# Sheet1.net
KiCad netlist of a schematic drawn in Altium Designer
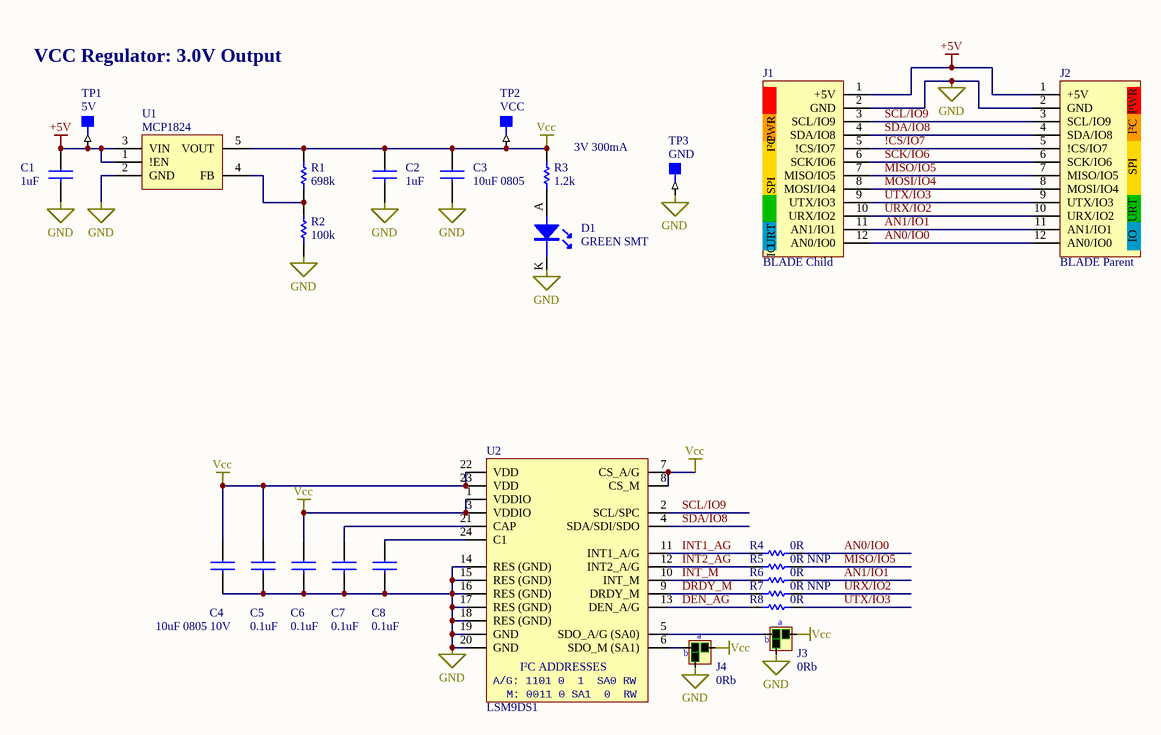
[diagram p0: Sheet1.SchDoc]

(export (version "E")
  (design (tool "Eeschema 10.0.6"))
  (components
    (comp (ref "C1")
      (value "1uF")
      (footprint "0603")
      (fields
        (field (name "4. DIGI-KEY PART NUMBER") "587-1251-2-ND")
        (field (name "3. MANUFACTURER PART NUMBER") "EMK107BJ105KA-T")
        (field (name "5. INTERNAL PART NUMBER") "100009")
        (field (name "7. MODIFIED BY") "JRL")
      )
      (libsource (lib "Blackline Master Schematic Library") (part "CAPACITOR NON-POLARIZED"))
    )
    (comp (ref "C2")
      (value "1uF")
      (footprint "0603")
      (fields
        (field (name "4. DIGI-KEY PART NUMBER") "587-1251-2-ND")
        (field (name "3. MANUFACTURER PART NUMBER") "EMK107BJ105KA-T")
        (field (name "5. INTERNAL PART NUMBER") "100009")
        (field (name "7. MODIFIED BY") "JRL")
      )
      (libsource (lib "Blackline Master Schematic Library") (part "CAPACITOR NON-POLARIZED"))
    )
    (comp (ref "C3")
      (value "10uF 0805")
      (footprint "0805")
      (fields
        (field (name "4. DIGI-KEY PART NUMBER") "587-1300-1-ND")
        (field (name "3. MANUFACTURER PART NUMBER") "LMK212BJ106KG-T")
        (field (name "5. INTERNAL PART NUMBER") "100006")
        (field (name "7. MODIFIED BY") "JRL")
      )
      (libsource (lib "Blackline Master Schematic Library") (part "CAPACITOR NON-POLARIZED"))
    )
    (comp (ref "C4")
      (value "10uF 0805 10V")
      (footprint "0805")
      (fields
        (field (name "4. DIGI-KEY PART NUMBER") "587-1300-1-ND")
        (field (name "3. MANUFACTURER PART NUMBER") "LMK212BJ106KG-T")
        (field (name "5. INTERNAL PART NUMBER") "100006")
        (field (name "7. MODIFIED BY") "JRL")
      )
      (libsource (lib "Blackline Master Schematic Library") (part "CAPACITOR NON-POLARIZED"))
    )
    (comp (ref "C5")
      (value "0.1uF")
      (footprint "0603")
      (fields
        (field (name "4. DIGI-KEY PART NUMBER") "445-1316-2-ND")
        (field (name "3. MANUFACTURER PART NUMBER") "C1608X7R1E104K")
        (field (name "5. INTERNAL PART NUMBER") "100130")
        (field (name "7. MODIFIED BY") "JRL")
      )
      (libsource (lib "Blackline Master Schematic Library") (part "CAPACITOR NON-POLARIZED"))
    )
    (comp (ref "C6")
      (value "0.1uF")
      (footprint "0603")
      (fields
        (field (name "4. DIGI-KEY PART NUMBER") "445-1316-2-ND")
        (field (name "3. MANUFACTURER PART NUMBER") "C1608X7R1E104K")
        (field (name "5. INTERNAL PART NUMBER") "100130")
        (field (name "7. MODIFIED BY") "JRL")
      )
      (libsource (lib "Blackline Master Schematic Library") (part "CAPACITOR NON-POLARIZED"))
    )
    (comp (ref "C7")
      (value "0.1uF")
      (footprint "0603")
      (fields
        (field (name "4. DIGI-KEY PART NUMBER") "445-1316-2-ND")
        (field (name "3. MANUFACTURER PART NUMBER") "C1608X7R1E104K")
        (field (name "5. INTERNAL PART NUMBER") "100130")
        (field (name "7. MODIFIED BY") "JRL")
      )
      (libsource (lib "Blackline Master Schematic Library") (part "CAPACITOR NON-POLARIZED"))
    )
    (comp (ref "C8")
      (value "0.1uF")
      (footprint "0603")
      (fields
        (field (name "4. DIGI-KEY PART NUMBER") "445-1316-2-ND")
        (field (name "3. MANUFACTURER PART NUMBER") "C1608X7R1E104K")
        (field (name "5. INTERNAL PART NUMBER") "100130")
        (field (name "7. MODIFIED BY") "JRL")
      )
      (libsource (lib "Blackline Master Schematic Library") (part "CAPACITOR NON-POLARIZED"))
    )
    (comp (ref "D1")
      (value "GREEN SMT")
      (footprint "0603 AK")
      (description "LED")
      (fields
        (field (name "3. MANUFACTURER PART NUMBER") "LTST-C190GKT")
        (field (name "4. DIGI-KEY PART NUMBER") "160-1183-1-ND")
        (field (name "7. MODIFIED BY") "JRL")
      )
      (libsource (lib "*") (part "LED T1-3/4"))
    )
    (comp (ref "J1")
      (value "BLADE Child")
      (footprint "HDR1X12 ENGENUICS CHILD")
      (fields
        (field (name "3. MANUFACTURER PART NUMBER") "68016-412HLF")
        (field (name "4. DIGI-KEY PART NUMBER") "609-3330-ND")
        (field (name "5. INTERNAL PART NUMBER") "100021")
        (field (name "7. MODIFIED BY") "JRL")
      )
      (libsource (lib "Engenuics Master Schematic Library") (part "CONN ENGENUICS BLADE CHILD"))
    )
    (comp (ref "J2")
      (value "BLADE Parent")
      (footprint "HDR1X12 ENGENUICS PARENT")
      (fields
        (field (name "3. MANUFACTURER PART NUMBER") "PPTC121LGBN-RC")
        (field (name "4. DIGI-KEY PART NUMBER") "S5448-ND")
        (field (name "5. INTERNAL PART NUMBER") "100031")
        (field (name "7. MODIFIED BY") "JRL")
      )
      (libsource (lib "Engenuics Master Schematic Library") (part "CONN ENGENUICS BLADE PARENT"))
    )
    (comp (ref "J3")
      (value "0Rb")
      (footprint "0603 SELECTOR")
      (fields
        (field (name "3. MANUFACTURER PART NUMBER") "CRCW06030000Z0EA")
        (field (name "4. DIGI-KEY PART NUMBER") "541-0.0GTR-ND")
        (field (name "5. INTERNAL PART NUMBER") "100075")
        (field (name "7. MODIFIED BY") "JRL")
      )
      (libsource (lib "Engenuics Master Schematic Library") (part "SWITCH RESISTOR SELECTOR"))
    )
    (comp (ref "J4")
      (value "0Rb")
      (footprint "0603 SELECTOR")
      (fields
        (field (name "3. MANUFACTURER PART NUMBER") "CRCW06030000Z0EA")
        (field (name "4. DIGI-KEY PART NUMBER") "541-0.0GTR-ND")
        (field (name "5. INTERNAL PART NUMBER") "100075")
        (field (name "7. MODIFIED BY") "JRL")
      )
      (libsource (lib "Engenuics Master Schematic Library") (part "SWITCH RESISTOR SELECTOR"))
    )
    (comp (ref "R1")
      (value "698k")
      (footprint "0603")
      (fields
        (field (name "4. DIGI-KEY PART NUMBER") "311-698KHRCT-ND")
        (field (name "3. MANUFACTURER PART NUMBER") "RC0603FR-07698KL")
        (field (name "5. INTERNAL PART NUMBER") "100087")
        (field (name "7. MODIFIED BY") "JRL")
      )
      (libsource (lib "Blackline Master Schematic Library") (part "RESISTOR"))
    )
    (comp (ref "R2")
      (value "100k")
      (footprint "0603")
      (fields
        (field (name "4. DIGI-KEY PART NUMBER") "RHM100KGCT-ND")
        (field (name "3. MANUFACTURER PART NUMBER") "MCR03EZPJ104")
        (field (name "5. INTERNAL PART NUMBER") "100078")
        (field (name "7. MODIFIED BY") "JRL")
      )
      (libsource (lib "Blackline Master Schematic Library") (part "RESISTOR"))
    )
    (comp (ref "R3")
      (value "1.2k")
      (footprint "0603")
      (fields
        (field (name "4. DIGI-KEY PART NUMBER") "RHM1.2KGCT-ND")
        (field (name "3. MANUFACTURER PART NUMBER") "MCR03EZPJ122")
        (field (name "5. INTERNAL PART NUMBER") "100076")
        (field (name "7. MODIFIED BY") "JRL")
      )
      (libsource (lib "Blackline Master Schematic Library") (part "RESISTOR"))
    )
    (comp (ref "R4")
      (value "0R")
      (footprint "0603")
      (fields
        (field (name "4. DIGI-KEY PART NUMBER") "541-0.0GTR-ND")
        (field (name "3. MANUFACTURER PART NUMBER") "CRCW06030000Z0EA")
        (field (name "5. INTERNAL PART NUMBER") "100075")
        (field (name "7. MODIFIED BY") "JRL")
      )
      (libsource (lib "Blackline Master Schematic Library") (part "RESISTOR"))
    )
    (comp (ref "R5")
      (value "0R NNP")
      (footprint "0603")
      (fields
        (field (name "4. DIGI-KEY PART NUMBER") "541-0.0GTR-ND")
        (field (name "3. MANUFACTURER PART NUMBER") "CRCW06030000Z0EA")
        (field (name "5. INTERNAL PART NUMBER") "100075")
        (field (name "7. MODIFIED BY") "JRL")
      )
      (libsource (lib "Blackline Master Schematic Library") (part "RESISTOR"))
    )
    (comp (ref "R6")
      (value "0R")
      (footprint "0603")
      (fields
        (field (name "4. DIGI-KEY PART NUMBER") "541-0.0GTR-ND")
        (field (name "3. MANUFACTURER PART NUMBER") "CRCW06030000Z0EA")
        (field (name "5. INTERNAL PART NUMBER") "100075")
        (field (name "7. MODIFIED BY") "JRL")
      )
      (libsource (lib "Blackline Master Schematic Library") (part "RESISTOR"))
    )
    (comp (ref "R7")
      (value "0R NNP")
      (footprint "0603")
      (fields
        (field (name "4. DIGI-KEY PART NUMBER") "541-0.0GTR-ND")
        (field (name "3. MANUFACTURER PART NUMBER") "CRCW06030000Z0EA")
        (field (name "5. INTERNAL PART NUMBER") "100075")
        (field (name "7. MODIFIED BY") "JRL")
      )
      (libsource (lib "Blackline Master Schematic Library") (part "RESISTOR"))
    )
    (comp (ref "R8")
      (value "0R")
      (footprint "0603")
      (fields
        (field (name "4. DIGI-KEY PART NUMBER") "541-0.0GTR-ND")
        (field (name "3. MANUFACTURER PART NUMBER") "CRCW06030000Z0EA")
        (field (name "5. INTERNAL PART NUMBER") "100075")
        (field (name "7. MODIFIED BY") "JRL")
      )
      (libsource (lib "Blackline Master Schematic Library") (part "RESISTOR"))
    )
    (comp (ref "TP1")
      (value "5V")
      (footprint "TEST POINT SMT")
      (fields (field (name "7. MODIFIED BY") "JRL"))
      (libsource (lib "Blackline Master Schematic Library") (part "TEST POINT SMT"))
    )
    (comp (ref "TP2")
      (value "VCC")
      (footprint "TEST POINT SMT")
      (fields (field (name "7. MODIFIED BY") "JRL"))
      (libsource (lib "Blackline Master Schematic Library") (part "TEST POINT SMT"))
    )
    (comp (ref "TP3")
      (value "GND")
      (footprint "TEST POINT SMT")
      (fields (field (name "7. MODIFIED BY") "JRL"))
      (libsource (lib "Blackline Master Schematic Library") (part "TEST POINT SMT"))
    )
    (comp (ref "U1")
      (value "MCP1824")
      (footprint "SOT23-5")
      (fields
        (field (name "3. MANUFACTURER PART NUMBER") "MCP1824T-ADJE/OT")
        (field (name "4. DIGI-KEY PART NUMBER") "MCP1824T-ADJE/OTCT-ND")
        (field (name "5. INTERNAL PART NUMBER") "100049")
        (field (name "7. MODIFIED BY") "JRL")
      )
      (libsource (lib "Device") (part "VREG MCP1824"))
    )
    (comp (ref "U2")
      (value "LSM9DS1")
      (footprint "LGA24 3.5 x 3mm LSM9DS1")
      (fields
        (field (name "3. MANUFACTURER PART NUMBER") "LSM9DS1TR")
        (field (name "4. DIGI-KEY PART NUMBER") "497-14946-1-ND")
        (field (name "7. MODIFIED BY") "JRL")
      )
      (libsource (lib "Engenuics Master Schematic Library") (part "IC IMU ST LSM9DS1"))
    )
  )
  (nets
    (net (code "1") (name "+5V") (class "Default")
      (node (ref "C1") (pin "1") (pinfunction "1_1") (pintype "passive"))
      (node (ref "J1") (pin "1") (pinfunction "+5V_1") (pintype "passive"))
      (node (ref "J2") (pin "1") (pinfunction "+5V_1") (pintype "passive"))
      (node (ref "TP1") (pin "1") (pinfunction "1_1") (pintype "input"))
      (node (ref "U1") (pin "1") (pinfunction "!EN_1") (pintype "passive"))
      (node (ref "U1") (pin "3") (pinfunction "VIN_3") (pintype "passive"))
    )
    (net (code "2") (name "/!CS{slash}IO7") (class "Default")
      (node (ref "J1") (pin "5") (pinfunction "!CS/IO7_5") (pintype "passive"))
      (node (ref "J2") (pin "5") (pinfunction "!CS/IO7_5") (pintype "passive"))
    )
    (net (code "3") (name "/AN0{slash}IO0") (class "Default")
      (node (ref "J1") (pin "12") (pinfunction "AN0/IO0_12") (pintype "passive"))
      (node (ref "J2") (pin "12") (pinfunction "AN0/IO0_12") (pintype "passive"))
      (node (ref "R4") (pin "1") (pinfunction "1_1") (pintype "passive"))
    )
    (net (code "4") (name "/AN1{slash}IO1") (class "Default")
      (node (ref "J1") (pin "11") (pinfunction "AN1/IO1_11") (pintype "passive"))
      (node (ref "J2") (pin "11") (pinfunction "AN1/IO1_11") (pintype "passive"))
      (node (ref "R6") (pin "1") (pinfunction "1_1") (pintype "passive"))
    )
    (net (code "5") (name "/DEN_AG") (class "Default")
      (node (ref "R8") (pin "2") (pinfunction "2_2") (pintype "passive"))
      (node (ref "U2") (pin "13") (pinfunction "DEN_A/G_13") (pintype "passive"))
    )
    (net (code "6") (name "/DRDY_M") (class "Default")
      (node (ref "R7") (pin "2") (pinfunction "2_2") (pintype "passive"))
      (node (ref "U2") (pin "9") (pinfunction "DRDY_M_9") (pintype "passive"))
    )
    (net (code "7") (name "/INT1_AG") (class "Default")
      (node (ref "R4") (pin "2") (pinfunction "2_2") (pintype "passive"))
      (node (ref "U2") (pin "11") (pinfunction "INT1_A/G_11") (pintype "passive"))
    )
    (net (code "8") (name "/INT2_AG") (class "Default")
      (node (ref "R5") (pin "2") (pinfunction "2_2") (pintype "passive"))
      (node (ref "U2") (pin "12") (pinfunction "INT2_A/G_12") (pintype "passive"))
    )
    (net (code "9") (name "/INT_M") (class "Default")
      (node (ref "R6") (pin "2") (pinfunction "2_2") (pintype "passive"))
      (node (ref "U2") (pin "10") (pinfunction "INT_M_10") (pintype "passive"))
    )
    (net (code "10") (name "/MISO{slash}IO5") (class "Default")
      (node (ref "J1") (pin "7") (pinfunction "MISO/IO5_7") (pintype "passive"))
      (node (ref "J2") (pin "7") (pinfunction "MISO/IO5_7") (pintype "passive"))
      (node (ref "R5") (pin "1") (pinfunction "1_1") (pintype "passive"))
    )
    (net (code "11") (name "/MOSI{slash}IO4") (class "Default")
      (node (ref "J1") (pin "8") (pinfunction "MOSI/IO4_8") (pintype "passive"))
      (node (ref "J2") (pin "8") (pinfunction "MOSI/IO4_8") (pintype "passive"))
    )
    (net (code "12") (name "/SCK{slash}IO6") (class "Default")
      (node (ref "J1") (pin "6") (pinfunction "SCK/IO6_6") (pintype "passive"))
      (node (ref "J2") (pin "6") (pinfunction "SCK/IO6_6") (pintype "passive"))
    )
    (net (code "13") (name "/SCL{slash}IO9") (class "Default")
      (node (ref "J1") (pin "3") (pinfunction "SCL/IO9_3") (pintype "passive"))
      (node (ref "J2") (pin "3") (pinfunction "SCL/IO9_3") (pintype "passive"))
      (node (ref "U2") (pin "2") (pinfunction "SCL/SPC_2") (pintype "passive"))
    )
    (net (code "14") (name "/SDA{slash}IO8") (class "Default")
      (node (ref "J1") (pin "4") (pinfunction "SDA/IO8_4") (pintype "passive"))
      (node (ref "J2") (pin "4") (pinfunction "SDA/IO8_4") (pintype "passive"))
      (node (ref "U2") (pin "4") (pinfunction "SDA/SDI/SDO_4") (pintype "passive"))
    )
    (net (code "15") (name "/URX{slash}IO2") (class "Default")
      (node (ref "J1") (pin "10") (pinfunction "URX/IO2_10") (pintype "passive"))
      (node (ref "J2") (pin "10") (pinfunction "URX/IO2_10") (pintype "passive"))
      (node (ref "R7") (pin "1") (pinfunction "1_1") (pintype "passive"))
    )
    (net (code "16") (name "/UTX{slash}IO3") (class "Default")
      (node (ref "J1") (pin "9") (pinfunction "UTX/IO3_9") (pintype "passive"))
      (node (ref "J2") (pin "9") (pinfunction "UTX/IO3_9") (pintype "passive"))
      (node (ref "R8") (pin "1") (pinfunction "1_1") (pintype "passive"))
    )
    (net (code "17") (name "GND") (class "Default")
      (node (ref "C1") (pin "2") (pinfunction "2_2") (pintype "passive"))
      (node (ref "C2") (pin "2") (pinfunction "2_2") (pintype "passive"))
      (node (ref "C3") (pin "2") (pinfunction "2_2") (pintype "passive"))
      (node (ref "C4") (pin "2") (pinfunction "2_2") (pintype "passive"))
      (node (ref "C5") (pin "2") (pinfunction "2_2") (pintype "passive"))
      (node (ref "C6") (pin "2") (pinfunction "2_2") (pintype "passive"))
      (node (ref "C7") (pin "2") (pinfunction "2_2") (pintype "passive"))
      (node (ref "C8") (pin "2") (pinfunction "2_2") (pintype "passive"))
      (node (ref "D1") (pin "K") (pinfunction "K1_K") (pintype "passive"))
      (node (ref "J1") (pin "2") (pinfunction "GND_2") (pintype "passive"))
      (node (ref "J2") (pin "2") (pinfunction "GND_2") (pintype "passive"))
      (node (ref "J3") (pin "3") (pinfunction "OUT2_3") (pintype "passive"))
      (node (ref "J4") (pin "3") (pinfunction "OUT2_3") (pintype "passive"))
      (node (ref "R2") (pin "2") (pinfunction "2_2") (pintype "passive"))
      (node (ref "TP3") (pin "1") (pinfunction "1_1") (pintype "input"))
      (node (ref "U1") (pin "2") (pinfunction "GND_2") (pintype "passive"))
      (node (ref "U2") (pin "14") (pinfunction "RES_(GND)_14") (pintype "passive"))
      (node (ref "U2") (pin "15") (pinfunction "RES_(GND)_15") (pintype "passive"))
      (node (ref "U2") (pin "16") (pinfunction "RES_(GND)_16") (pintype "passive"))
      (node (ref "U2") (pin "17") (pinfunction "RES_(GND)_17") (pintype "passive"))
      (node (ref "U2") (pin "18") (pinfunction "RES_(GND)_18") (pintype "passive"))
      (node (ref "U2") (pin "19") (pinfunction "GND_19") (pintype "passive"))
      (node (ref "U2") (pin "20") (pinfunction "GND_20") (pintype "passive"))
    )
    (net (code "18") (name "Net-(D1-A1)") (class "Default")
      (node (ref "D1") (pin "A") (pinfunction "A1_A") (pintype "passive"))
      (node (ref "R3") (pin "1") (pinfunction "1_1") (pintype "passive"))
    )
    (net (code "19") (name "Net-(J3-IN)") (class "Default")
      (node (ref "J3") (pin "1") (pinfunction "IN_1") (pintype "passive"))
      (node (ref "U2") (pin "5") (pinfunction "SDO_A/G_(SA0)_5") (pintype "passive"))
    )
    (net (code "20") (name "Net-(J4-IN)") (class "Default")
      (node (ref "J4") (pin "1") (pinfunction "IN_1") (pintype "passive"))
      (node (ref "U2") (pin "6") (pinfunction "SDO_M_(SA1)_6") (pintype "passive"))
    )
    (net (code "21") (name "Net-(U1-FB)") (class "Default")
      (node (ref "R1") (pin "1") (pinfunction "1_1") (pintype "passive"))
      (node (ref "R2") (pin "1") (pinfunction "1_1") (pintype "passive"))
      (node (ref "U1") (pin "4") (pinfunction "FB_4") (pintype "passive"))
    )
    (net (code "22") (name "Net-(U2-C1)") (class "Default")
      (node (ref "C8") (pin "1") (pinfunction "1_1") (pintype "passive"))
      (node (ref "U2") (pin "24") (pinfunction "C1_24") (pintype "passive"))
    )
    (net (code "23") (name "Net-(U2-CAP)") (class "Default")
      (node (ref "C7") (pin "1") (pinfunction "1_1") (pintype "passive"))
      (node (ref "U2") (pin "21") (pinfunction "CAP_21") (pintype "passive"))
    )
    (net (code "24") (name "Vcc") (class "Default")
      (node (ref "C2") (pin "1") (pinfunction "1_1") (pintype "passive"))
      (node (ref "C3") (pin "1") (pinfunction "1_1") (pintype "passive"))
      (node (ref "C4") (pin "1") (pinfunction "1_1") (pintype "passive"))
      (node (ref "C5") (pin "1") (pinfunction "1_1") (pintype "passive"))
      (node (ref "C6") (pin "1") (pinfunction "1_1") (pintype "passive"))
      (node (ref "J3") (pin "2") (pinfunction "OUT1_2") (pintype "passive"))
      (node (ref "J4") (pin "2") (pinfunction "OUT1_2") (pintype "passive"))
      (node (ref "R1") (pin "2") (pinfunction "2_2") (pintype "passive"))
      (node (ref "R3") (pin "2") (pinfunction "2_2") (pintype "passive"))
      (node (ref "TP2") (pin "1") (pinfunction "1_1") (pintype "input"))
      (node (ref "U1") (pin "5") (pinfunction "VOUT_5") (pintype "passive"))
      (node (ref "U2") (pin "1") (pinfunction "VDDIO_1") (pintype "passive"))
      (node (ref "U2") (pin "22") (pinfunction "VDD_22") (pintype "passive"))
      (node (ref "U2") (pin "23") (pinfunction "VDD_23") (pintype "passive"))
      (node (ref "U2") (pin "3") (pinfunction "VDDIO_3") (pintype "passive"))
      (node (ref "U2") (pin "7") (pinfunction "CS_A/G_7") (pintype "passive"))
      (node (ref "U2") (pin "8") (pinfunction "CS_M_8") (pintype "passive"))
    )
  )
)
